# ProProject_Buck-Boost_1_fin_1.net
KiCad netlist of a schematic drawn in EasyEDA Pro
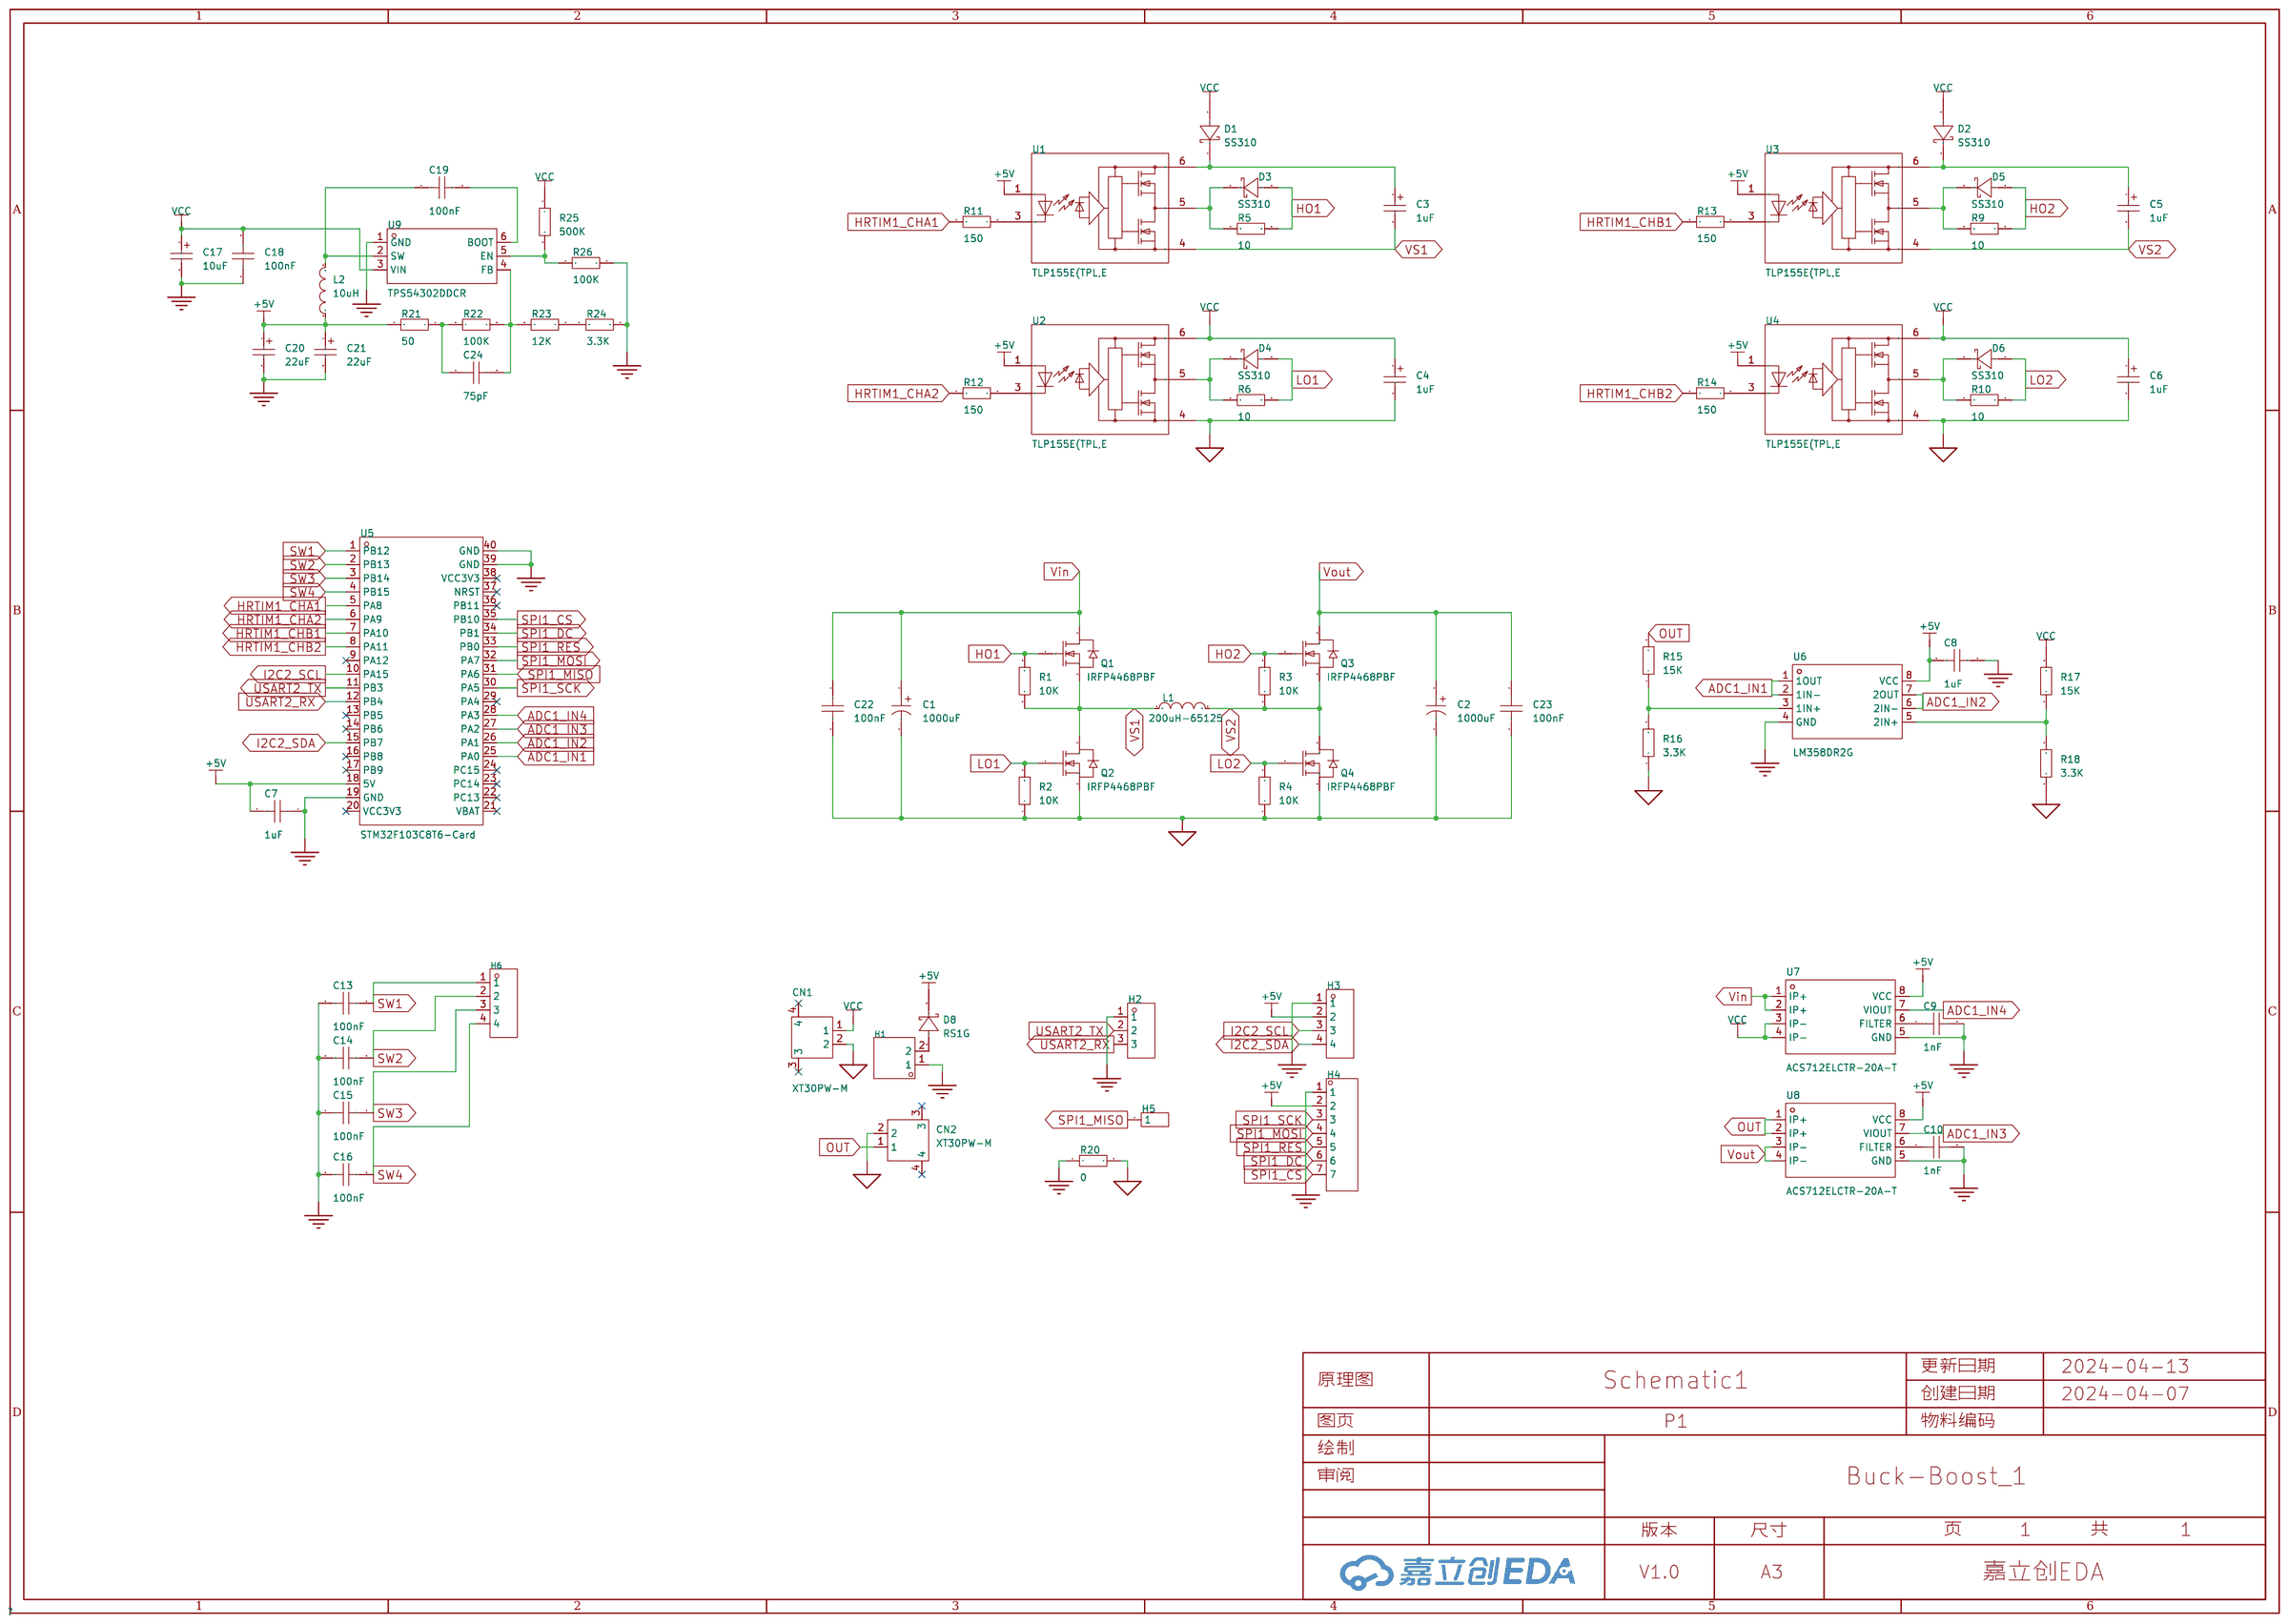
[diagram p0: schematic sheet]

(export (version "E")
  (design (tool "Eeschema 10.0.6"))
  (components
    (comp (ref "C1")
      (value "1000uF")
      (footprint "easyedapro:CAP-TH_BD16.0-P7.50-D1.5-FD")
      (description "容值:470uF;精度:±20%;额定电压:120V;纹波电流:-;等效串联电阻:-;")
      (fields (field (name "Manufacturer Part") "KF102M050I250A") (field (name "Manufacturer") "CapXon(丰宾)"))
      (libsource (lib "easyedapro") (part "ERS2BM471L35OT"))
    )
    (comp (ref "C2")
      (value "1000uF")
      (footprint "easyedapro:CAP-TH_BD16.0-P7.50-D1.5-FD")
      (description "容值:470uF;精度:±20%;额定电压:120V;纹波电流:-;等效串联电阻:-;")
      (fields (field (name "Manufacturer Part") "KF102M050I250A") (field (name "Manufacturer") "CapXon(丰宾)"))
      (libsource (lib "easyedapro") (part "ERS2BM471L35OT"))
    )
    (comp (ref "C3")
      (value "1uF")
      (footprint "easyedapro:CASE-A_3216")
      (description "容值:1uF;精度:±10%;额定电压:35V;等效串联电阻:7.5Ω@100kHz;")
      (fields (field (name "Manufacturer Part") "TAJA105K035RNJ") (field (name "Manufacturer") "Kyocera AVX"))
      (libsource (lib "easyedapro") (part "TAJA105K035RNJ"))
    )
    (comp (ref "C4")
      (value "1uF")
      (footprint "easyedapro:CASE-A_3216")
      (description "容值:1uF;精度:±10%;额定电压:35V;等效串联电阻:7.5Ω@100kHz;")
      (fields (field (name "Manufacturer Part") "TAJA105K035RNJ") (field (name "Manufacturer") "Kyocera AVX"))
      (libsource (lib "easyedapro") (part "TAJA105K035RNJ"))
    )
    (comp (ref "C5")
      (value "1uF")
      (footprint "easyedapro:CASE-A_3216")
      (description "容值:1uF;精度:±10%;额定电压:35V;等效串联电阻:7.5Ω@100kHz;")
      (fields (field (name "Manufacturer Part") "TAJA105K035RNJ") (field (name "Manufacturer") "Kyocera AVX"))
      (libsource (lib "easyedapro") (part "TAJA105K035RNJ"))
    )
    (comp (ref "C6")
      (value "1uF")
      (footprint "easyedapro:CASE-A_3216")
      (description "容值:1uF;精度:±10%;额定电压:35V;等效串联电阻:7.5Ω@100kHz;")
      (fields (field (name "Manufacturer Part") "TAJA105K035RNJ") (field (name "Manufacturer") "Kyocera AVX"))
      (libsource (lib "easyedapro") (part "TAJA105K035RNJ"))
    )
    (comp (ref "C7")
      (value "1uF")
      (footprint "easyedapro:C0805")
      (libsource (lib "easyedapro") (part "CapAcitance"))
    )
    (comp (ref "C8")
      (value "1uF")
      (footprint "easyedapro:C0805")
      (libsource (lib "easyedapro") (part "CapAcitance"))
    )
    (comp (ref "C9")
      (value "1nF")
      (footprint "easyedapro:C0805")
      (libsource (lib "easyedapro") (part "CapAcitance"))
    )
    (comp (ref "C10")
      (value "1nF")
      (footprint "easyedapro:C0805")
      (libsource (lib "easyedapro") (part "CapAcitance"))
    )
    (comp (ref "C13")
      (value "100nF")
      (footprint "easyedapro:C0805")
      (libsource (lib "easyedapro") (part "CapAcitance"))
    )
    (comp (ref "C14")
      (value "100nF")
      (footprint "easyedapro:C0805")
      (libsource (lib "easyedapro") (part "CapAcitance"))
    )
    (comp (ref "C15")
      (value "100nF")
      (footprint "easyedapro:C0805")
      (libsource (lib "easyedapro") (part "CapAcitance"))
    )
    (comp (ref "C16")
      (value "100nF")
      (footprint "easyedapro:C0805")
      (libsource (lib "easyedapro") (part "CapAcitance"))
    )
    (comp (ref "C17")
      (value "10uF")
      (footprint "easyedapro:CAP-SMD_L3.5-W2.8-R-RD")
      (description "容值:10uF;精度:±10%;额定电压:25V;等效串联电阻:2.5Ω@100kHz;")
      (fields (field (name "Manufacturer Part") "TAJB106K025RNJ") (field (name "Manufacturer") "Kyocera AVX"))
      (libsource (lib "easyedapro") (part "TAJB106K025RNJ"))
    )
    (comp (ref "C18")
      (value "100nF")
      (footprint "easyedapro:C0805")
      (libsource (lib "easyedapro") (part "CapAcitance"))
    )
    (comp (ref "C19")
      (value "100nF")
      (footprint "easyedapro:C0805")
      (libsource (lib "easyedapro") (part "CapAcitance"))
    )
    (comp (ref "C20")
      (value "22uF")
      (footprint "easyedapro:CASE-B_3528")
      (description "容值:22uF;精度:±10%;额定电压:16V;等效串联电阻:2.3Ω@100kHz;")
      (fields (field (name "Manufacturer Part") "TAJB226K016RNJ") (field (name "Manufacturer") "Kyocera AVX"))
      (libsource (lib "easyedapro") (part "TAJB226K016RNJ"))
    )
    (comp (ref "C21")
      (value "22uF")
      (footprint "easyedapro:CASE-B_3528")
      (description "容值:22uF;精度:±10%;额定电压:16V;等效串联电阻:2.3Ω@100kHz;")
      (fields (field (name "Manufacturer Part") "TAJB226K016RNJ") (field (name "Manufacturer") "Kyocera AVX"))
      (libsource (lib "easyedapro") (part "TAJB226K016RNJ"))
    )
    (comp (ref "C22")
      (value "100nF")
      (footprint "easyedapro:C0805")
      (libsource (lib "easyedapro") (part "CapAcitance"))
    )
    (comp (ref "C23")
      (value "100nF")
      (footprint "easyedapro:C0805")
      (libsource (lib "easyedapro") (part "CapAcitance"))
    )
    (comp (ref "C24")
      (value "75pF")
      (footprint "easyedapro:C0805")
      (libsource (lib "easyedapro") (part "CapAcitance"))
    )
    (comp (ref "CN1")
      (value "XT30PW-M")
      (footprint "easyedapro:CONN-TH_XT30PW-M")
      (description "类别:-;类型1:-;")
      (fields (field (name "Manufacturer") "AMASS(艾迈斯)"))
      (libsource (lib "easyedapro") (part "XT30PW-M"))
    )
    (comp (ref "CN2")
      (value "XT30PW-M")
      (footprint "easyedapro:CONN-TH_XT30PW-M")
      (description "类别:-;类型1:-;")
      (fields (field (name "Manufacturer") "AMASS(艾迈斯)"))
      (libsource (lib "easyedapro") (part "XT30PW-M"))
    )
    (comp (ref "D1")
      (value "SS310")
      (footprint "easyedapro:SMC_L6.9-W5.9-LS7.9-RD")
      (fields (field (name "Manufacturer") "MDD"))
      (libsource (lib "easyedapro") (part "SS56_C5161914"))
    )
    (comp (ref "D2")
      (value "SS310")
      (footprint "easyedapro:SMC_L6.9-W5.9-LS7.9-RD")
      (fields (field (name "Manufacturer") "MDD"))
      (libsource (lib "easyedapro") (part "SS56_C5161914"))
    )
    (comp (ref "D3")
      (value "SS310")
      (footprint "easyedapro:SMC_L6.9-W5.9-LS7.9-RD")
      (fields (field (name "Manufacturer") "MDD"))
      (libsource (lib "easyedapro") (part "SS56_C5161914"))
    )
    (comp (ref "D4")
      (value "SS310")
      (footprint "easyedapro:SMC_L6.9-W5.9-LS7.9-RD")
      (fields (field (name "Manufacturer") "MDD"))
      (libsource (lib "easyedapro") (part "SS56_C5161914"))
    )
    (comp (ref "D5")
      (value "SS310")
      (footprint "easyedapro:SMC_L6.9-W5.9-LS7.9-RD")
      (fields (field (name "Manufacturer") "MDD"))
      (libsource (lib "easyedapro") (part "SS56_C5161914"))
    )
    (comp (ref "D6")
      (value "SS310")
      (footprint "easyedapro:SMC_L6.9-W5.9-LS7.9-RD")
      (fields (field (name "Manufacturer") "MDD"))
      (libsource (lib "easyedapro") (part "SS56_C5161914"))
    )
    (comp (ref "D8")
      (value "RS1G")
      (footprint "easyedapro:SMC_L6.9-W5.9-LS7.9-RD")
      (fields (field (name "Manufacturer") "宏迦橙"))
      (libsource (lib "easyedapro") (part "SS56_C5161914"))
    )
    (comp (ref "H1")
      (value "~")
      (footprint "easyedapro:HDR-TH_2P-P2.54-V-M-1")
      (libsource (lib "easyedapro") (part "210S-1*2P L=11.6MMGold-plated black"))
    )
    (comp (ref "H2")
      (value "~")
      (footprint "easyedapro:HDR-TH_3P-P2.54-V-M")
      (libsource (lib "easyedapro") (part "PZ254V-11-03P_C2937625"))
    )
    (comp (ref "H3")
      (value "~")
      (footprint "easyedapro:HDR-TH_4P-P2.54-V-F")
      (libsource (lib "easyedapro") (part "2.54-1*4P母"))
    )
    (comp (ref "H4")
      (value "~")
      (footprint "easyedapro:HDR-TH_7P-P2.54-V-F")
      (libsource (lib "easyedapro") (part "220S-1*7P H=8.5MM Ytype Gold-plated"))
    )
    (comp (ref "H5")
      (value "~")
      (footprint "easyedapro:HDR-TH_1P-V-M_XKB_X4611WV-01I-C28D40")
      (libsource (lib "easyedapro") (part "HDR_1x1"))
    )
    (comp (ref "H6")
      (value "~")
      (footprint "easyedapro:HDR-TH_4P-P2.54-V-M")
      (libsource (lib "easyedapro") (part "PZ254V-11-04P"))
    )
    (comp (ref "L1")
      (value "200uH-65125")
      (footprint "easyedapro:IND-TH_200UH-65125")
      (libsource (lib "easyedapro") (part "200UH-65125"))
    )
    (comp (ref "L2")
      (value "10uH")
      (footprint "easyedapro:IND-SMD_L7.3-W6.8")
      (description "电感值:10uH;精度:±20%;额定电流:4.5A;饱和电流(Isat):5.5A;类型:一体成型电感;")
      (fields (field (name "Manufacturer Part") "FXL0420-100-M") (field (name "Manufacturer") "cjiang(长江微电)"))
      (libsource (lib "easyedapro") (part "FXL0630-100-M"))
    )
    (comp (ref "Q1")
      (value "IRFP4468PBF")
      (footprint "easyedapro:TO-247AC-3_L15.8-W5.0-P5.46-L")
      (fields (field (name "Manufacturer") "Infineon(英飞凌)"))
      (libsource (lib "easyedapro") (part "IRFP4468PBF"))
    )
    (comp (ref "Q2")
      (value "IRFP4468PBF")
      (footprint "easyedapro:TO-247AC-3_L15.8-W5.0-P5.46-L")
      (fields (field (name "Manufacturer") "Infineon(英飞凌)"))
      (libsource (lib "easyedapro") (part "IRFP4468PBF"))
    )
    (comp (ref "Q3")
      (value "IRFP4468PBF")
      (footprint "easyedapro:TO-247AC-3_L15.8-W5.0-P5.46-L")
      (fields (field (name "Manufacturer") "Infineon(英飞凌)"))
      (libsource (lib "easyedapro") (part "IRFP4468PBF"))
    )
    (comp (ref "Q4")
      (value "IRFP4468PBF")
      (footprint "easyedapro:TO-247AC-3_L15.8-W5.0-P5.46-L")
      (fields (field (name "Manufacturer") "Infineon(英飞凌)"))
      (libsource (lib "easyedapro") (part "IRFP4468PBF"))
    )
    (comp (ref "R1") (value "10K") (footprint "easyedapro:R0805") (libsource (lib "easyedapro") (part "电阻")))
    (comp (ref "R2") (value "10K") (footprint "easyedapro:R0805") (libsource (lib "easyedapro") (part "电阻")))
    (comp (ref "R3") (value "10K") (footprint "easyedapro:R0805") (libsource (lib "easyedapro") (part "电阻")))
    (comp (ref "R4") (value "10K") (footprint "easyedapro:R0805") (libsource (lib "easyedapro") (part "电阻")))
    (comp (ref "R5") (value "10") (footprint "easyedapro:R0805") (libsource (lib "easyedapro") (part "电阻")))
    (comp (ref "R6") (value "10") (footprint "easyedapro:R0805") (libsource (lib "easyedapro") (part "电阻")))
    (comp (ref "R9") (value "10") (footprint "easyedapro:R0805") (libsource (lib "easyedapro") (part "电阻")))
    (comp (ref "R10") (value "10") (footprint "easyedapro:R0805") (libsource (lib "easyedapro") (part "电阻")))
    (comp (ref "R11") (value "150") (footprint "easyedapro:R0805") (libsource (lib "easyedapro") (part "电阻")))
    (comp (ref "R12") (value "150") (footprint "easyedapro:R0805") (libsource (lib "easyedapro") (part "电阻")))
    (comp (ref "R13") (value "150") (footprint "easyedapro:R0805") (libsource (lib "easyedapro") (part "电阻")))
    (comp (ref "R14") (value "150") (footprint "easyedapro:R0805") (libsource (lib "easyedapro") (part "电阻")))
    (comp (ref "R15") (value "15K") (footprint "easyedapro:R0805") (libsource (lib "easyedapro") (part "电阻")))
    (comp (ref "R16")
      (value "3.3K")
      (footprint "easyedapro:R0805")
      (libsource (lib "easyedapro") (part "电阻"))
    )
    (comp (ref "R17") (value "15K") (footprint "easyedapro:R0805") (libsource (lib "easyedapro") (part "电阻")))
    (comp (ref "R18")
      (value "3.3K")
      (footprint "easyedapro:R0805")
      (libsource (lib "easyedapro") (part "电阻"))
    )
    (comp (ref "R20") (value "0") (footprint "easyedapro:R0805") (libsource (lib "easyedapro") (part "电阻")))
    (comp (ref "R21") (value "50") (footprint "easyedapro:R0805") (libsource (lib "easyedapro") (part "电阻")))
    (comp (ref "R22")
      (value "100K")
      (footprint "easyedapro:R0805")
      (libsource (lib "easyedapro") (part "电阻"))
    )
    (comp (ref "R23") (value "12K") (footprint "easyedapro:R0805") (libsource (lib "easyedapro") (part "电阻")))
    (comp (ref "R24")
      (value "3.3K")
      (footprint "easyedapro:R0805")
      (libsource (lib "easyedapro") (part "电阻"))
    )
    (comp (ref "R25")
      (value "500K")
      (footprint "easyedapro:R0805")
      (libsource (lib "easyedapro") (part "电阻"))
    )
    (comp (ref "R26")
      (value "100K")
      (footprint "easyedapro:R0805")
      (libsource (lib "easyedapro") (part "电阻"))
    )
    (comp (ref "U1")
      (value "TLP155E(TPL,E")
      (footprint "easyedapro:OPTO-SMD-5_L3.7-W4.6-P1.27-LS7.0-BR")
      (description "输入类型:DC;电源电压:10V~30V;共模瞬变抗扰度CMTI:15kV/us;传播延迟tpLH/tpHL:170ns；170ns;")
      (fields (field (name "Manufacturer") "TOSHIBA(东芝)"))
      (libsource (lib "easyedapro") (part "TLP155E(TPL,E"))
    )
    (comp (ref "U2")
      (value "TLP155E(TPL,E")
      (footprint "easyedapro:OPTO-SMD-5_L3.7-W4.6-P1.27-LS7.0-BR")
      (description "输入类型:DC;电源电压:10V~30V;共模瞬变抗扰度CMTI:15kV/us;传播延迟tpLH/tpHL:170ns；170ns;")
      (fields (field (name "Manufacturer") "TOSHIBA(东芝)"))
      (libsource (lib "easyedapro") (part "TLP155E(TPL,E"))
    )
    (comp (ref "U3")
      (value "TLP155E(TPL,E")
      (footprint "easyedapro:OPTO-SMD-5_L3.7-W4.6-P1.27-LS7.0-BR")
      (description "输入类型:DC;电源电压:10V~30V;共模瞬变抗扰度CMTI:15kV/us;传播延迟tpLH/tpHL:170ns；170ns;")
      (fields (field (name "Manufacturer") "TOSHIBA(东芝)"))
      (libsource (lib "easyedapro") (part "TLP155E(TPL,E"))
    )
    (comp (ref "U4")
      (value "TLP155E(TPL,E")
      (footprint "easyedapro:OPTO-SMD-5_L3.7-W4.6-P1.27-LS7.0-BR")
      (description "输入类型:DC;电源电压:10V~30V;共模瞬变抗扰度CMTI:15kV/us;传播延迟tpLH/tpHL:170ns；170ns;")
      (fields (field (name "Manufacturer") "TOSHIBA(东芝)"))
      (libsource (lib "easyedapro") (part "TLP155E(TPL,E"))
    )
    (comp (ref "U5")
      (value "STM32F103C8T6-Card")
      (footprint "easyedapro:CONN-TH_L53.3-W22.9_STM32F103C8T6-CARD")
      (libsource (lib "easyedapro") (part "STM32F103C8T6-CARD"))
    )
    (comp (ref "U6")
      (value "LM358DR2G")
      (footprint "easyedapro:SOIC-8_L5.0-W4.0-P1.27-LS6.0-BL")
      (description "放大器数:双路;增益带宽积(GBP):1MHz;输入偏置电流(Ib):45nA;压摆率(SR):-;带宽(-3db):-;")
      (fields (field (name "Manufacturer") "onsemi(安森美)"))
      (libsource (lib "easyedapro") (part "LM358DR2G"))
    )
    (comp (ref "U7")
      (value "ACS712ELCTR-20A-T")
      (footprint "easyedapro:SOIC-8_L4.9-W3.9-P1.27-LS6.0-BL")
      (description "电流测量范围:20A;灵敏度:100mV/A;")
      (fields (field (name "Manufacturer") "ALLEGRO(美国埃戈罗)"))
      (libsource (lib "easyedapro") (part "ACS712ELCTR-20A-T"))
    )
    (comp (ref "U8")
      (value "ACS712ELCTR-20A-T")
      (footprint "easyedapro:SOIC-8_L4.9-W3.9-P1.27-LS6.0-BL")
      (description "电流测量范围:20A;灵敏度:100mV/A;")
      (fields (field (name "Manufacturer") "ALLEGRO(美国埃戈罗)"))
      (libsource (lib "easyedapro") (part "ACS712ELCTR-20A-T"))
    )
    (comp (ref "U9")
      (value "TPS54302DDCR")
      (footprint "easyedapro:SOT-23-6_L2.9-W1.6-P0.95-LS2.8-BL")
      (description "功能类型:降压型;输出类型:可调;输入电压:4.5V~28V;输出电压:596mV~28V;输出电流(最大值):3A;")
      (fields (field (name "Manufacturer") "TI(德州仪器)"))
      (libsource (lib "easyedapro") (part "TPS54302DDCR_C311983"))
    )
  )
  (nets
    (net (code "1") (name "+5V") (class "Default")
      (node (ref "C20") (pin "1") (pinfunction "1_1") (pintype "input"))
      (node (ref "C21") (pin "1") (pinfunction "1_1") (pintype "input"))
      (node (ref "C7") (pin "2") (pinfunction "2_2") (pintype "input"))
      (node (ref "C8") (pin "1") (pinfunction "1_1") (pintype "input"))
      (node (ref "D8") (pin "1") (pinfunction "K_1") (pintype "unspecified"))
      (node (ref "H3") (pin "2") (pinfunction "2_2") (pintype "unspecified"))
      (node (ref "H4") (pin "2") (pinfunction "2_2") (pintype "unspecified"))
      (node (ref "L2") (pin "1") (pinfunction "1_1") (pintype "unspecified"))
      (node (ref "R21") (pin "2") (pinfunction "2_2") (pintype "input"))
      (node (ref "U1") (pin "1") (pinfunction "AN_1") (pintype "unspecified"))
      (node (ref "U2") (pin "1") (pinfunction "AN_1") (pintype "unspecified"))
      (node (ref "U3") (pin "1") (pinfunction "AN_1") (pintype "unspecified"))
      (node (ref "U4") (pin "1") (pinfunction "AN_1") (pintype "unspecified"))
      (node (ref "U5") (pin "18") (pinfunction "5V_18") (pintype "unspecified"))
      (node (ref "U6") (pin "8") (pinfunction "VCC_8") (pintype "unspecified"))
      (node (ref "U7") (pin "8") (pinfunction "VCC_8") (pintype "unspecified"))
      (node (ref "U8") (pin "8") (pinfunction "VCC_8") (pintype "unspecified"))
    )
    (net (code "2") (name "ADC1_IN1") (class "Default")
      (node (ref "U5") (pin "25") (pinfunction "PA0_25") (pintype "unspecified"))
      (node (ref "U6") (pin "1") (pinfunction "1OUT_1") (pintype "unspecified"))
      (node (ref "U6") (pin "2") (pinfunction "1IN-_2") (pintype "unspecified"))
    )
    (net (code "3") (name "ADC1_IN2") (class "Default")
      (node (ref "U5") (pin "26") (pinfunction "PA1_26") (pintype "unspecified"))
      (node (ref "U6") (pin "6") (pinfunction "2IN-_6") (pintype "unspecified"))
      (node (ref "U6") (pin "7") (pinfunction "2OUT_7") (pintype "unspecified"))
    )
    (net (code "4") (name "ADC1_IN3") (class "Default")
      (node (ref "U5") (pin "27") (pinfunction "PA2_27") (pintype "unspecified"))
      (node (ref "U8") (pin "7") (pinfunction "VIOUT_7") (pintype "unspecified"))
    )
    (net (code "5") (name "ADC1_IN4") (class "Default")
      (node (ref "U5") (pin "28") (pinfunction "PA3_28") (pintype "unspecified"))
      (node (ref "U7") (pin "7") (pinfunction "VIOUT_7") (pintype "unspecified"))
    )
    (net (code "6") (name "AGND") (class "Default")
      (node (ref "C1") (pin "2") (pinfunction "2_2") (pintype "input"))
      (node (ref "C2") (pin "2") (pinfunction "2_2") (pintype "input"))
      (node (ref "C22") (pin "2") (pinfunction "2_2") (pintype "input"))
      (node (ref "C23") (pin "2") (pinfunction "2_2") (pintype "input"))
      (node (ref "C4") (pin "2") (pinfunction "2_2") (pintype "input"))
      (node (ref "C6") (pin "2") (pinfunction "2_2") (pintype "input"))
      (node (ref "CN1") (pin "2") (pinfunction "2_2") (pintype "unspecified"))
      (node (ref "CN2") (pin "2") (pinfunction "2_2") (pintype "unspecified"))
      (node (ref "Q2") (pin "3") (pinfunction "S_3") (pintype "unspecified"))
      (node (ref "Q4") (pin "3") (pinfunction "S_3") (pintype "unspecified"))
      (node (ref "R16") (pin "1") (pinfunction "1_1") (pintype "input"))
      (node (ref "R18") (pin "1") (pinfunction "1_1") (pintype "input"))
      (node (ref "R2") (pin "1") (pinfunction "1_1") (pintype "input"))
      (node (ref "R20") (pin "2") (pinfunction "2_2") (pintype "input"))
      (node (ref "R4") (pin "1") (pinfunction "1_1") (pintype "input"))
      (node (ref "U2") (pin "4") (pinfunction "GND_4") (pintype "unspecified"))
      (node (ref "U4") (pin "4") (pinfunction "GND_4") (pintype "unspecified"))
    )
    (net (code "7") (name "GND") (class "Default")
      (node (ref "C10") (pin "2") (pinfunction "2_2") (pintype "input"))
      (node (ref "C13") (pin "1") (pinfunction "1_1") (pintype "input"))
      (node (ref "C14") (pin "1") (pinfunction "1_1") (pintype "input"))
      (node (ref "C15") (pin "1") (pinfunction "1_1") (pintype "input"))
      (node (ref "C16") (pin "1") (pinfunction "1_1") (pintype "input"))
      (node (ref "C17") (pin "2") (pinfunction "2_2") (pintype "input"))
      (node (ref "C18") (pin "1") (pinfunction "1_1") (pintype "input"))
      (node (ref "C20") (pin "2") (pinfunction "2_2") (pintype "input"))
      (node (ref "C21") (pin "2") (pinfunction "2_2") (pintype "input"))
      (node (ref "C7") (pin "1") (pinfunction "1_1") (pintype "input"))
      (node (ref "C8") (pin "2") (pinfunction "2_2") (pintype "input"))
      (node (ref "C9") (pin "2") (pinfunction "2_2") (pintype "input"))
      (node (ref "H1") (pin "1") (pinfunction "1_1") (pintype "input"))
      (node (ref "H2") (pin "1") (pinfunction "1_1") (pintype "input"))
      (node (ref "H3") (pin "1") (pinfunction "1_1") (pintype "unspecified"))
      (node (ref "H4") (pin "1") (pinfunction "1_1") (pintype "unspecified"))
      (node (ref "R20") (pin "1") (pinfunction "1_1") (pintype "input"))
      (node (ref "R24") (pin "2") (pinfunction "2_2") (pintype "input"))
      (node (ref "R26") (pin "2") (pinfunction "2_2") (pintype "input"))
      (node (ref "U5") (pin "19") (pinfunction "GND_19") (pintype "unspecified"))
      (node (ref "U5") (pin "39") (pinfunction "GND_39") (pintype "unspecified"))
      (node (ref "U5") (pin "40") (pinfunction "GND_40") (pintype "unspecified"))
      (node (ref "U6") (pin "4") (pinfunction "GND_4") (pintype "unspecified"))
      (node (ref "U7") (pin "5") (pinfunction "GND_5") (pintype "unspecified"))
      (node (ref "U8") (pin "5") (pinfunction "GND_5") (pintype "unspecified"))
      (node (ref "U9") (pin "1") (pinfunction "GND_1") (pintype "unspecified"))
    )
    (net (code "8") (name "HO1") (class "Default")
      (node (ref "D3") (pin "2") (pinfunction "A_2") (pintype "unspecified"))
      (node (ref "Q1") (pin "1") (pinfunction "G_1") (pintype "unspecified"))
      (node (ref "R1") (pin "2") (pinfunction "2_2") (pintype "input"))
      (node (ref "R5") (pin "2") (pinfunction "2_2") (pintype "input"))
    )
    (net (code "9") (name "HO2") (class "Default")
      (node (ref "D5") (pin "2") (pinfunction "A_2") (pintype "unspecified"))
      (node (ref "Q3") (pin "1") (pinfunction "G_1") (pintype "unspecified"))
      (node (ref "R3") (pin "2") (pinfunction "2_2") (pintype "input"))
      (node (ref "R9") (pin "2") (pinfunction "2_2") (pintype "input"))
    )
    (net (code "10") (name "HRTIM1_CHA1") (class "Default")
      (node (ref "R11") (pin "1") (pinfunction "1_1") (pintype "input"))
      (node (ref "U5") (pin "5") (pinfunction "PA8_5") (pintype "unspecified"))
    )
    (net (code "11") (name "HRTIM1_CHA2") (class "Default")
      (node (ref "R12") (pin "1") (pinfunction "1_1") (pintype "input"))
      (node (ref "U5") (pin "6") (pinfunction "PA9_6") (pintype "unspecified"))
    )
    (net (code "12") (name "HRTIM1_CHB1") (class "Default")
      (node (ref "R13") (pin "1") (pinfunction "1_1") (pintype "input"))
      (node (ref "U5") (pin "7") (pinfunction "PA10_7") (pintype "unspecified"))
    )
    (net (code "13") (name "HRTIM1_CHB2") (class "Default")
      (node (ref "R14") (pin "1") (pinfunction "1_1") (pintype "input"))
      (node (ref "U5") (pin "8") (pinfunction "PA11_8") (pintype "unspecified"))
    )
    (net (code "14") (name "I2C2_SCL") (class "Default")
      (node (ref "H3") (pin "3") (pinfunction "3_3") (pintype "unspecified"))
      (node (ref "U5") (pin "10") (pinfunction "PA15_10") (pintype "unspecified"))
    )
    (net (code "15") (name "I2C2_SDA") (class "Default")
      (node (ref "H3") (pin "4") (pinfunction "4_4") (pintype "unspecified"))
      (node (ref "U5") (pin "15") (pinfunction "PB7_15") (pintype "unspecified"))
    )
    (net (code "16") (name "LO1") (class "Default")
      (node (ref "D4") (pin "2") (pinfunction "A_2") (pintype "unspecified"))
      (node (ref "Q2") (pin "1") (pinfunction "G_1") (pintype "unspecified"))
      (node (ref "R2") (pin "2") (pinfunction "2_2") (pintype "input"))
      (node (ref "R6") (pin "2") (pinfunction "2_2") (pintype "input"))
    )
    (net (code "17") (name "LO2") (class "Default")
      (node (ref "D6") (pin "2") (pinfunction "A_2") (pintype "unspecified"))
      (node (ref "Q4") (pin "1") (pinfunction "G_1") (pintype "unspecified"))
      (node (ref "R10") (pin "2") (pinfunction "2_2") (pintype "input"))
      (node (ref "R4") (pin "2") (pinfunction "2_2") (pintype "input"))
    )
    (net (code "18") (name "Net-(C24-Pad1)") (class "Default")
      (node (ref "C24") (pin "1") (pinfunction "1_1") (pintype "input"))
      (node (ref "R21") (pin "1") (pinfunction "1_1") (pintype "input"))
      (node (ref "R22") (pin "2") (pinfunction "2_2") (pintype "input"))
    )
    (net (code "19") (name "Net-(D1-K)") (class "Default")
      (node (ref "C3") (pin "1") (pinfunction "1_1") (pintype "input"))
      (node (ref "D1") (pin "1") (pinfunction "K_1") (pintype "unspecified"))
      (node (ref "U1") (pin "6") (pinfunction "VCC_6") (pintype "unspecified"))
    )
    (net (code "20") (name "Net-(D2-K)") (class "Default")
      (node (ref "C5") (pin "1") (pinfunction "1_1") (pintype "input"))
      (node (ref "D2") (pin "1") (pinfunction "K_1") (pintype "unspecified"))
      (node (ref "U3") (pin "6") (pinfunction "VCC_6") (pintype "unspecified"))
    )
    (net (code "21") (name "Net-(D3-K)") (class "Default")
      (node (ref "D3") (pin "1") (pinfunction "K_1") (pintype "unspecified"))
      (node (ref "R5") (pin "1") (pinfunction "1_1") (pintype "input"))
      (node (ref "U1") (pin "5") (pinfunction "VO_5") (pintype "unspecified"))
    )
    (net (code "22") (name "Net-(D4-K)") (class "Default")
      (node (ref "D4") (pin "1") (pinfunction "K_1") (pintype "unspecified"))
      (node (ref "R6") (pin "1") (pinfunction "1_1") (pintype "input"))
      (node (ref "U2") (pin "5") (pinfunction "VO_5") (pintype "unspecified"))
    )
    (net (code "23") (name "Net-(D5-K)") (class "Default")
      (node (ref "D5") (pin "1") (pinfunction "K_1") (pintype "unspecified"))
      (node (ref "R9") (pin "1") (pinfunction "1_1") (pintype "input"))
      (node (ref "U3") (pin "5") (pinfunction "VO_5") (pintype "unspecified"))
    )
    (net (code "24") (name "Net-(D6-K)") (class "Default")
      (node (ref "D6") (pin "1") (pinfunction "K_1") (pintype "unspecified"))
      (node (ref "R10") (pin "1") (pinfunction "1_1") (pintype "input"))
      (node (ref "U4") (pin "5") (pinfunction "VO_5") (pintype "unspecified"))
    )
    (net (code "25") (name "Net-(D8-A)") (class "Default")
      (node (ref "D8") (pin "2") (pinfunction "A_2") (pintype "unspecified"))
      (node (ref "H1") (pin "2") (pinfunction "2_2") (pintype "input"))
    )
    (net (code "26") (name "Net-(R23-Pad1)") (class "Default")
      (node (ref "R23") (pin "1") (pinfunction "1_1") (pintype "input"))
      (node (ref "R24") (pin "1") (pinfunction "1_1") (pintype "input"))
    )
    (net (code "27") (name "Net-(U1-CAT)") (class "Default")
      (node (ref "R11") (pin "2") (pinfunction "2_2") (pintype "input"))
      (node (ref "U1") (pin "3") (pinfunction "CAT_3") (pintype "unspecified"))
    )
    (net (code "28") (name "Net-(U2-CAT)") (class "Default")
      (node (ref "R12") (pin "2") (pinfunction "2_2") (pintype "input"))
      (node (ref "U2") (pin "3") (pinfunction "CAT_3") (pintype "unspecified"))
    )
    (net (code "29") (name "Net-(U3-CAT)") (class "Default")
      (node (ref "R13") (pin "2") (pinfunction "2_2") (pintype "input"))
      (node (ref "U3") (pin "3") (pinfunction "CAT_3") (pintype "unspecified"))
    )
    (net (code "30") (name "Net-(U4-CAT)") (class "Default")
      (node (ref "R14") (pin "2") (pinfunction "2_2") (pintype "input"))
      (node (ref "U4") (pin "3") (pinfunction "CAT_3") (pintype "unspecified"))
    )
    (net (code "31") (name "Net-(U6-1IN+)") (class "Default")
      (node (ref "R15") (pin "1") (pinfunction "1_1") (pintype "input"))
      (node (ref "R16") (pin "2") (pinfunction "2_2") (pintype "input"))
      (node (ref "U6") (pin "3") (pinfunction "1IN+_3") (pintype "unspecified"))
    )
    (net (code "32") (name "Net-(U6-2IN+)") (class "Default")
      (node (ref "R17") (pin "1") (pinfunction "1_1") (pintype "input"))
      (node (ref "R18") (pin "2") (pinfunction "2_2") (pintype "input"))
      (node (ref "U6") (pin "5") (pinfunction "2IN+_5") (pintype "unspecified"))
    )
    (net (code "33") (name "Net-(U7-FILTER)") (class "Default")
      (node (ref "C9") (pin "1") (pinfunction "1_1") (pintype "input"))
      (node (ref "U7") (pin "6") (pinfunction "FILTER_6") (pintype "unspecified"))
    )
    (net (code "34") (name "Net-(U8-FILTER)") (class "Default")
      (node (ref "C10") (pin "1") (pinfunction "1_1") (pintype "input"))
      (node (ref "U8") (pin "6") (pinfunction "FILTER_6") (pintype "unspecified"))
    )
    (net (code "35") (name "Net-(U9-BOOT)") (class "Default")
      (node (ref "C19") (pin "2") (pinfunction "2_2") (pintype "input"))
      (node (ref "U9") (pin "6") (pinfunction "BOOT_6") (pintype "unspecified"))
    )
    (net (code "36") (name "Net-(U9-EN)") (class "Default")
      (node (ref "R25") (pin "2") (pinfunction "2_2") (pintype "input"))
      (node (ref "R26") (pin "1") (pinfunction "1_1") (pintype "input"))
      (node (ref "U9") (pin "5") (pinfunction "EN_5") (pintype "unspecified"))
    )
    (net (code "37") (name "Net-(U9-FB)") (class "Default")
      (node (ref "C24") (pin "2") (pinfunction "2_2") (pintype "input"))
      (node (ref "R22") (pin "1") (pinfunction "1_1") (pintype "input"))
      (node (ref "R23") (pin "2") (pinfunction "2_2") (pintype "input"))
      (node (ref "U9") (pin "4") (pinfunction "FB_4") (pintype "unspecified"))
    )
    (net (code "38") (name "Net-(U9-SW)") (class "Default")
      (node (ref "C19") (pin "1") (pinfunction "1_1") (pintype "input"))
      (node (ref "L2") (pin "2") (pinfunction "2_2") (pintype "unspecified"))
      (node (ref "U9") (pin "2") (pinfunction "SW_2") (pintype "unspecified"))
    )
    (net (code "39") (name "OUT") (class "Default")
      (node (ref "CN2") (pin "1") (pinfunction "1_1") (pintype "unspecified"))
      (node (ref "R15") (pin "2") (pinfunction "2_2") (pintype "input"))
      (node (ref "U8") (pin "1") (pinfunction "IP+_1") (pintype "unspecified"))
      (node (ref "U8") (pin "2") (pinfunction "IP+_2") (pintype "unspecified"))
    )
    (net (code "40") (name "SPI1_CS") (class "Default")
      (node (ref "H4") (pin "7") (pinfunction "7_7") (pintype "unspecified"))
      (node (ref "U5") (pin "35") (pinfunction "PB10_35") (pintype "unspecified"))
    )
    (net (code "41") (name "SPI1_DC") (class "Default")
      (node (ref "H4") (pin "6") (pinfunction "6_6") (pintype "unspecified"))
      (node (ref "U5") (pin "34") (pinfunction "PB1_34") (pintype "unspecified"))
    )
    (net (code "42") (name "SPI1_MISO") (class "Default")
      (node (ref "H5") (pin "1") (pinfunction "1_1") (pintype "unspecified"))
      (node (ref "U5") (pin "31") (pinfunction "PA6_31") (pintype "unspecified"))
    )
    (net (code "43") (name "SPI1_MOSI") (class "Default")
      (node (ref "H4") (pin "4") (pinfunction "4_4") (pintype "unspecified"))
      (node (ref "U5") (pin "32") (pinfunction "PA7_32") (pintype "unspecified"))
    )
    (net (code "44") (name "SPI1_RES") (class "Default")
      (node (ref "H4") (pin "5") (pinfunction "5_5") (pintype "unspecified"))
      (node (ref "U5") (pin "33") (pinfunction "PB0_33") (pintype "unspecified"))
    )
    (net (code "45") (name "SPI1_SCK") (class "Default")
      (node (ref "H4") (pin "3") (pinfunction "3_3") (pintype "unspecified"))
      (node (ref "U5") (pin "30") (pinfunction "PA5_30") (pintype "unspecified"))
    )
    (net (code "46") (name "SW1") (class "Default")
      (node (ref "C13") (pin "2") (pinfunction "2_2") (pintype "input"))
      (node (ref "H6") (pin "1") (pinfunction "1_1") (pintype "input"))
      (node (ref "U5") (pin "1") (pinfunction "PB12_1") (pintype "unspecified"))
    )
    (net (code "47") (name "SW2") (class "Default")
      (node (ref "C14") (pin "2") (pinfunction "2_2") (pintype "input"))
      (node (ref "H6") (pin "2") (pinfunction "2_2") (pintype "input"))
      (node (ref "U5") (pin "2") (pinfunction "PB13_2") (pintype "unspecified"))
    )
    (net (code "48") (name "SW3") (class "Default")
      (node (ref "C15") (pin "2") (pinfunction "2_2") (pintype "input"))
      (node (ref "H6") (pin "3") (pinfunction "3_3") (pintype "input"))
      (node (ref "U5") (pin "3") (pinfunction "PB14_3") (pintype "unspecified"))
    )
    (net (code "49") (name "SW4") (class "Default")
      (node (ref "C16") (pin "2") (pinfunction "2_2") (pintype "input"))
      (node (ref "H6") (pin "4") (pinfunction "4_4") (pintype "input"))
      (node (ref "U5") (pin "4") (pinfunction "PB15_4") (pintype "unspecified"))
    )
    (net (code "50") (name "USART2_RX") (class "Default")
      (node (ref "H2") (pin "3") (pinfunction "3_3") (pintype "input"))
      (node (ref "U5") (pin "12") (pinfunction "PB4_12") (pintype "unspecified"))
    )
    (net (code "51") (name "USART2_TX") (class "Default")
      (node (ref "H2") (pin "2") (pinfunction "2_2") (pintype "input"))
      (node (ref "U5") (pin "11") (pinfunction "PB3_11") (pintype "unspecified"))
    )
    (net (code "52") (name "VCC") (class "Default")
      (node (ref "C17") (pin "1") (pinfunction "1_1") (pintype "input"))
      (node (ref "C18") (pin "2") (pinfunction "2_2") (pintype "input"))
      (node (ref "C4") (pin "1") (pinfunction "1_1") (pintype "input"))
      (node (ref "C6") (pin "1") (pinfunction "1_1") (pintype "input"))
      (node (ref "CN1") (pin "1") (pinfunction "1_1") (pintype "unspecified"))
      (node (ref "D1") (pin "2") (pinfunction "A_2") (pintype "unspecified"))
      (node (ref "D2") (pin "2") (pinfunction "A_2") (pintype "unspecified"))
      (node (ref "R17") (pin "2") (pinfunction "2_2") (pintype "input"))
      (node (ref "R25") (pin "1") (pinfunction "1_1") (pintype "input"))
      (node (ref "U2") (pin "6") (pinfunction "VCC_6") (pintype "unspecified"))
      (node (ref "U4") (pin "6") (pinfunction "VCC_6") (pintype "unspecified"))
      (node (ref "U7") (pin "3") (pinfunction "IP-_3") (pintype "unspecified"))
      (node (ref "U7") (pin "4") (pinfunction "IP-_4") (pintype "unspecified"))
      (node (ref "U9") (pin "3") (pinfunction "VIN_3") (pintype "unspecified"))
    )
    (net (code "53") (name "VS1") (class "Default")
      (node (ref "C3") (pin "2") (pinfunction "2_2") (pintype "input"))
      (node (ref "L1") (pin "1") (pinfunction "1_1") (pintype "input"))
      (node (ref "Q1") (pin "3") (pinfunction "S_3") (pintype "unspecified"))
      (node (ref "Q2") (pin "2") (pinfunction "D_2") (pintype "unspecified"))
      (node (ref "R1") (pin "1") (pinfunction "1_1") (pintype "input"))
      (node (ref "U1") (pin "4") (pinfunction "GND_4") (pintype "unspecified"))
    )
    (net (code "54") (name "VS2") (class "Default")
      (node (ref "C5") (pin "2") (pinfunction "2_2") (pintype "input"))
      (node (ref "L1") (pin "2") (pinfunction "2_2") (pintype "input"))
      (node (ref "Q3") (pin "3") (pinfunction "S_3") (pintype "unspecified"))
      (node (ref "Q4") (pin "2") (pinfunction "D_2") (pintype "unspecified"))
      (node (ref "R3") (pin "1") (pinfunction "1_1") (pintype "input"))
      (node (ref "U3") (pin "4") (pinfunction "GND_4") (pintype "unspecified"))
    )
    (net (code "55") (name "Vin") (class "Default")
      (node (ref "C1") (pin "1") (pinfunction "1_1") (pintype "input"))
      (node (ref "C22") (pin "1") (pinfunction "1_1") (pintype "input"))
      (node (ref "Q1") (pin "2") (pinfunction "D_2") (pintype "unspecified"))
      (node (ref "U7") (pin "1") (pinfunction "IP+_1") (pintype "unspecified"))
      (node (ref "U7") (pin "2") (pinfunction "IP+_2") (pintype "unspecified"))
    )
    (net (code "56") (name "Vout") (class "Default")
      (node (ref "C2") (pin "1") (pinfunction "1_1") (pintype "input"))
      (node (ref "C23") (pin "1") (pinfunction "1_1") (pintype "input"))
      (node (ref "Q3") (pin "2") (pinfunction "D_2") (pintype "unspecified"))
      (node (ref "U8") (pin "3") (pinfunction "IP-_3") (pintype "unspecified"))
      (node (ref "U8") (pin "4") (pinfunction "IP-_4") (pintype "unspecified"))
    )
    (net (code "57") (name "unconnected-(CN1-Pad3)") (class "Default")
      (node (ref "CN1") (pin "3") (pinfunction "3_3") (pintype "unspecified+no_connect"))
    )
    (net (code "58") (name "unconnected-(CN1-Pad4)") (class "Default")
      (node (ref "CN1") (pin "4") (pinfunction "4_4") (pintype "unspecified+no_connect"))
    )
    (net (code "59") (name "unconnected-(CN2-Pad3)") (class "Default")
      (node (ref "CN2") (pin "3") (pinfunction "3_3") (pintype "unspecified+no_connect"))
    )
    (net (code "60") (name "unconnected-(CN2-Pad4)") (class "Default")
      (node (ref "CN2") (pin "4") (pinfunction "4_4") (pintype "unspecified+no_connect"))
    )
    (net (code "61") (name "unconnected-(U5-NRST-Pad37)") (class "Default")
      (node (ref "U5") (pin "37") (pinfunction "NRST_37") (pintype "unspecified+no_connect"))
    )
    (net (code "62") (name "unconnected-(U5-PA4-Pad29)") (class "Default")
      (node (ref "U5") (pin "29") (pinfunction "PA4_29") (pintype "unspecified+no_connect"))
    )
    (net (code "63") (name "unconnected-(U5-PA12-Pad9)") (class "Default")
      (node (ref "U5") (pin "9") (pinfunction "PA12_9") (pintype "unspecified+no_connect"))
    )
    (net (code "64") (name "unconnected-(U5-PB5-Pad13)") (class "Default")
      (node (ref "U5") (pin "13") (pinfunction "PB5_13") (pintype "unspecified+no_connect"))
    )
    (net (code "65") (name "unconnected-(U5-PB6-Pad14)") (class "Default")
      (node (ref "U5") (pin "14") (pinfunction "PB6_14") (pintype "unspecified+no_connect"))
    )
    (net (code "66") (name "unconnected-(U5-PB8-Pad16)") (class "Default")
      (node (ref "U5") (pin "16") (pinfunction "PB8_16") (pintype "unspecified+no_connect"))
    )
    (net (code "67") (name "unconnected-(U5-PB9-Pad17)") (class "Default")
      (node (ref "U5") (pin "17") (pinfunction "PB9_17") (pintype "unspecified+no_connect"))
    )
    (net (code "68") (name "unconnected-(U5-PB11-Pad36)") (class "Default")
      (node (ref "U5") (pin "36") (pinfunction "PB11_36") (pintype "unspecified+no_connect"))
    )
    (net (code "69") (name "unconnected-(U5-PC13-Pad22)") (class "Default")
      (node (ref "U5") (pin "22") (pinfunction "PC13_22") (pintype "unspecified+no_connect"))
    )
    (net (code "70") (name "unconnected-(U5-PC14-Pad23)") (class "Default")
      (node (ref "U5") (pin "23") (pinfunction "PC14_23") (pintype "unspecified+no_connect"))
    )
    (net (code "71") (name "unconnected-(U5-PC15-Pad24)") (class "Default")
      (node (ref "U5") (pin "24") (pinfunction "PC15_24") (pintype "unspecified+no_connect"))
    )
    (net (code "72") (name "unconnected-(U5-VBAT-Pad21)") (class "Default")
      (node (ref "U5") (pin "21") (pinfunction "VBAT_21") (pintype "unspecified+no_connect"))
    )
    (net (code "73") (name "unconnected-(U5-VCC3V3-Pad20)") (class "Default")
      (node (ref "U5") (pin "20") (pinfunction "VCC3V3_20") (pintype "unspecified+no_connect"))
    )
    (net (code "74") (name "unconnected-(U5-VCC3V3-Pad38)") (class "Default")
      (node (ref "U5") (pin "38") (pinfunction "VCC3V3_38") (pintype "unspecified+no_connect"))
    )
  )
)
